# Main.net
KiCad netlist of a schematic drawn in Altium Designer
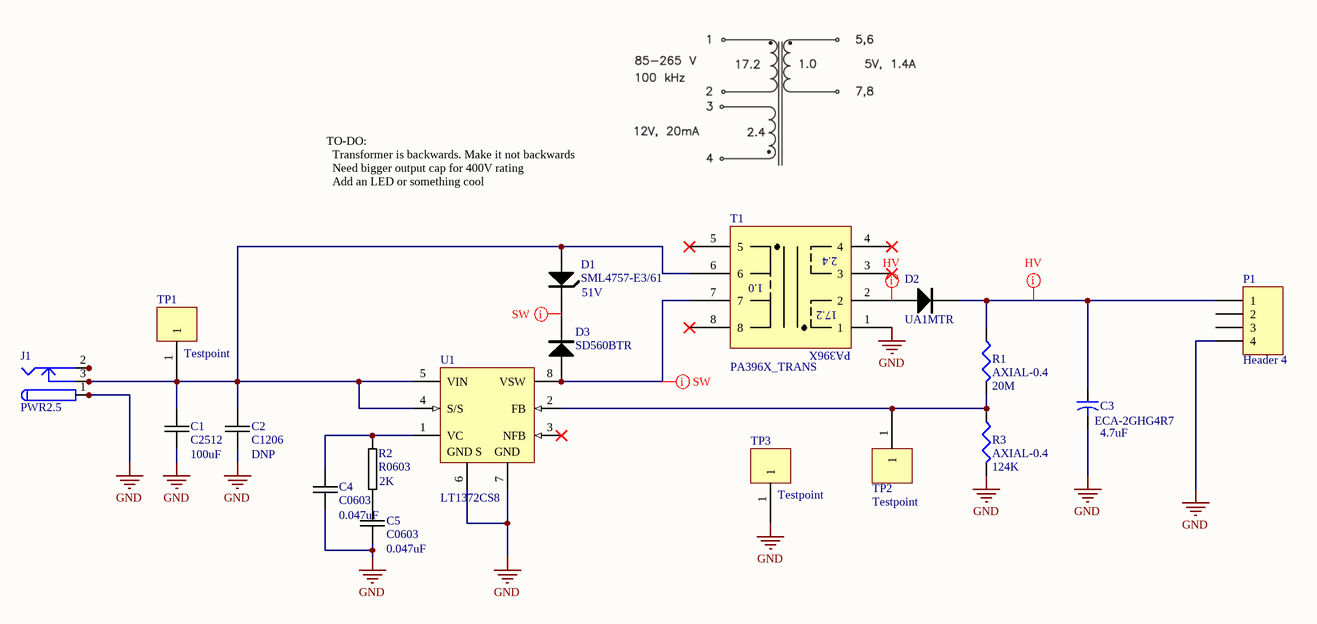
[diagram p0: Main.SchDoc]

(export (version "E")
  (design (tool "Eeschema 10.0.6"))
  (components
    (comp (ref "C1")
      (value "C2512")
      (footprint "2512R-GENERIC")
      (fields (field (name "ALTIUM_VALUE") "100uF"))
      (libsource (lib "vh_altium_library") (part "0805C-TBD"))
    )
    (comp (ref "C2")
      (value "C1206")
      (footprint "1206C-GENERIC")
      (description "CAPACITOR 0805 CERAMIC VALUE TO BE DETERMINED")
      (fields (field (name "ALTIUM_VALUE") "DNP"))
      (libsource (lib "vh_altium_library") (part "0805C-TBD"))
    )
    (comp (ref "C3")
      (value "4.7uF")
      (footprint "CAP_10MM")
      (description "Capacitor")
      (fields (field (name "PARTNUMBER") "ECA-2GHG4R7") (field (name "PUBLISHER") "Altium Limited"))
      (libsource (lib "Miscellaneous Devices") (part "Cap2"))
    )
    (comp (ref "C4")
      (value "C0603")
      (footprint "0603C-TBD")
      (description "CAPACITOR 0603 CERAMIC VALUE TO BE DETERMINED")
      (fields (field (name "ALTIUM_VALUE") "0.047uF"))
      (libsource (lib "vh_altium_library") (part "0603C-TBD"))
    )
    (comp (ref "C5")
      (value "C0603")
      (footprint "0603C-TBD")
      (description "CAPACITOR 0603 CERAMIC VALUE TO BE DETERMINED")
      (fields (field (name "ALTIUM_VALUE") "0.047uF"))
      (libsource (lib "vh_altium_library") (part "0603C-TBD"))
    )
    (comp (ref "D1")
      (value "SML4757-E3/61")
      (footprint "DO214AA")
      (description "GENERIC ZENER DIODE")
      (fields (field (name "ALTIUM_VALUE") "51V"))
      (libsource (lib "vh_altium_library") (part "DIODE-ZENER-GENERIC"))
    )
    (comp (ref "D2")
      (value "UA1MTR")
      (footprint "DO214AA")
      (description "GENERIC DIODE")
      (libsource (lib "vh_altium_library") (part "DIODE-GENERIC"))
    )
    (comp (ref "D3")
      (value "SD560BTR")
      (footprint "DO214AA")
      (description "GENERIC DIODE")
      (libsource (lib "vh_altium_library") (part "DIODE-GENERIC"))
    )
    (comp (ref "J1")
      (value "PWR2.5")
      (footprint "Miscellaneous Connectors:KLD-0202")
      (description "Low Voltage Power Supply Connector")
      (fields (field (name "PUBLISHER") "Altium Limited"))
      (libsource (lib "Miscellaneous Connectors") (part "PWR2.5"))
    )
    (comp (ref "P1")
      (value "Header 4")
      (footprint "HDR1X4")
      (description "Header, 4-Pin")
      (fields (field (name "PUBLISHER") "Altium Limited"))
      (libsource (lib "Miscellaneous Connectors") (part "Header 4"))
    )
    (comp (ref "R1")
      (value "AXIAL-0.4")
      (footprint "AXIAL-0.4")
      (description "Resistor")
      (fields (field (name "ALTIUM_VALUE") "20M") (field (name "PUBLISHER") "Altium Limited"))
      (libsource (lib "Miscellaneous Devices") (part "Res3"))
    )
    (comp (ref "R2")
      (value "R0603")
      (footprint "0603R-TBD")
      (description "RESISTOR 0603 VALUE TO BE DETERMINED")
      (fields (field (name "ALTIUM_VALUE") "2K"))
      (libsource (lib "vh_altium_library") (part "0603R-TBD"))
    )
    (comp (ref "R3")
      (value "AXIAL-0.4")
      (footprint "AXIAL-0.4")
      (description "Resistor")
      (fields (field (name "ALTIUM_VALUE") "124K") (field (name "PUBLISHER") "Altium Limited"))
      (libsource (lib "Miscellaneous Devices") (part "Res3"))
    )
    (comp (ref "T1")
      (value "PA396X_TRANS")
      (footprint "Trans18x15.6")
      (libsource (lib "Schematic_Components") (part "PA396X_TRANS"))
    )
    (comp (ref "TP1")
      (value "Testpoint")
      (footprint "1206_Testpoint")
      (libsource (lib "") (part "Testpoint_1"))
    )
    (comp (ref "TP2")
      (value "Testpoint")
      (footprint "1206_Testpoint")
      (libsource (lib "Schematic_Components") (part "Testpoint"))
    )
    (comp (ref "TP3")
      (value "Testpoint")
      (footprint "1206_Testpoint")
      (libsource (lib "") (part "Testpoint_1"))
    )
    (comp (ref "U1")
      (value "LT1372CS8")
      (footprint "LT-S8-8_N")
      (description "500 kHz High Efficiency 1.5 A Switching Regulator, 8-pin SOIC (S8-8), 0 to 125 degC")
      (fields (field (name "MANUFACTURER") "Linear Technology"))
      (libsource (lib "Linear Technology Power Management Switching Regulator LT1074-LT8705") (part "LT1372CS8"))
    )
  )
  (nets
    (net (code "1") (name "GND") (class "Default")
      (node (ref "C1") (pin "2") (pintype "passive"))
      (node (ref "C2") (pin "2") (pintype "passive"))
      (node (ref "C3") (pin "2") (pinfunction "2_2") (pintype "passive"))
      (node (ref "C4") (pin "2") (pintype "passive"))
      (node (ref "C5") (pin "2") (pintype "passive"))
      (node (ref "J1") (pin "1") (pinfunction "1_1") (pintype "power_in"))
      (node (ref "J1") (pin "1A") (pinfunction "1A_1A") (pintype "power_in"))
      (node (ref "J1") (pin "1B") (pinfunction "1B_1B") (pintype "power_in"))
      (node (ref "P1") (pin "4") (pinfunction "4_4") (pintype "passive"))
      (node (ref "R3") (pin "2") (pinfunction "2_2") (pintype "passive"))
      (node (ref "T1") (pin "1") (pinfunction "1_1") (pintype "passive"))
      (node (ref "TP3") (pin "1") (pinfunction "1_1") (pintype "passive"))
      (node (ref "U1") (pin "6") (pinfunction "GND_S_6") (pintype "power_in"))
      (node (ref "U1") (pin "7") (pinfunction "GND_7") (pintype "power_in"))
    )
    (net (code "2") (name "Net-(C3-Pad1)") (class "Default")
      (node (ref "C3") (pin "1") (pinfunction "1_1") (pintype "passive"))
      (node (ref "D2") (pin "K") (pinfunction "K_K") (pintype "passive"))
      (node (ref "P1") (pin "1") (pinfunction "1_1") (pintype "passive"))
      (node (ref "R1") (pin "1") (pinfunction "1_1") (pintype "passive"))
    )
    (net (code "3") (name "Net-(C5-Pad1)") (class "Default")
      (node (ref "C5") (pin "1") (pintype "passive"))
      (node (ref "R2") (pin "2") (pintype "passive"))
    )
    (net (code "4") (name "Net-(D1-PadK)") (class "Default")
      (node (ref "D1") (pin "K") (pinfunction "K_K") (pintype "passive"))
      (node (ref "D3") (pin "K") (pinfunction "K_K") (pintype "passive"))
    )
    (net (code "5") (name "Net-(D2-PadA)") (class "Default")
      (node (ref "D2") (pin "A") (pinfunction "A_A") (pintype "passive"))
      (node (ref "T1") (pin "2") (pinfunction "2_2") (pintype "passive"))
    )
    (net (code "6") (name "Net-(J1-Pad2)") (class "Default")
      (node (ref "J1") (pin "2") (pinfunction "2_2") (pintype "power_in"))
      (node (ref "J1") (pin "2A") (pinfunction "2A_2A") (pintype "power_in"))
      (node (ref "J1") (pin "2B") (pinfunction "2B_2B") (pintype "power_in"))
    )
    (net (code "7") (name "Net-(U1-FB)") (class "Default")
      (node (ref "R1") (pin "2") (pinfunction "2_2") (pintype "passive"))
      (node (ref "R3") (pin "1") (pinfunction "1_1") (pintype "passive"))
      (node (ref "TP2") (pin "1") (pinfunction "1_1") (pintype "passive"))
      (node (ref "U1") (pin "2") (pinfunction "FB_2") (pintype "input"))
    )
    (net (code "8") (name "Net-(U1-S{slash}S)") (class "Default")
      (node (ref "C1") (pin "1") (pintype "passive"))
      (node (ref "C2") (pin "1") (pintype "passive"))
      (node (ref "D1") (pin "A") (pinfunction "A_A") (pintype "passive"))
      (node (ref "J1") (pin "3") (pinfunction "3_3") (pintype "power_in"))
      (node (ref "J1") (pin "3A") (pinfunction "3A_3A") (pintype "power_in"))
      (node (ref "J1") (pin "3B") (pinfunction "3B_3B") (pintype "power_in"))
      (node (ref "T1") (pin "6") (pinfunction "6_6") (pintype "passive"))
      (node (ref "TP1") (pin "1") (pinfunction "1_1") (pintype "passive"))
      (node (ref "U1") (pin "4") (pinfunction "S/S_4") (pintype "input"))
      (node (ref "U1") (pin "5") (pinfunction "VIN_5") (pintype "power_in"))
    )
    (net (code "9") (name "Net-(U1-VC)") (class "Default")
      (node (ref "C4") (pin "1") (pintype "passive"))
      (node (ref "R2") (pin "1") (pintype "passive"))
      (node (ref "U1") (pin "1") (pinfunction "VC_1") (pintype "passive"))
    )
    (net (code "10") (name "Net-(U1-VSW)") (class "Default")
      (node (ref "D3") (pin "A") (pinfunction "A_A") (pintype "passive"))
      (node (ref "T1") (pin "7") (pinfunction "7_7") (pintype "passive"))
      (node (ref "U1") (pin "8") (pinfunction "VSW_8") (pintype "power_in"))
    )
    (net (code "11") (name "unconnected-(P1-Pad2)") (class "Default")
      (node (ref "P1") (pin "2") (pinfunction "2_2") (pintype "passive"))
    )
    (net (code "12") (name "unconnected-(P1-Pad3)") (class "Default")
      (node (ref "P1") (pin "3") (pinfunction "3_3") (pintype "passive"))
    )
    (net (code "13") (name "unconnected-(T1-Pad3)") (class "Default")
      (node (ref "T1") (pin "3") (pinfunction "3_3") (pintype "passive+no_connect"))
    )
    (net (code "14") (name "unconnected-(T1-Pad4)") (class "Default")
      (node (ref "T1") (pin "4") (pinfunction "4_4") (pintype "passive+no_connect"))
    )
    (net (code "15") (name "unconnected-(T1-Pad5)") (class "Default")
      (node (ref "T1") (pin "5") (pinfunction "5_5") (pintype "passive+no_connect"))
    )
    (net (code "16") (name "unconnected-(T1-Pad8)") (class "Default")
      (node (ref "T1") (pin "8") (pinfunction "8_8") (pintype "passive+no_connect"))
    )
    (net (code "17") (name "unconnected-(U1-NFB-Pad3)") (class "Default")
      (node (ref "U1") (pin "3") (pinfunction "NFB_3") (pintype "input+no_connect"))
    )
  )
)
